# USB-C_Power_Delivery_Board.net
KiCad netlist of a schematic drawn in Altium Designer
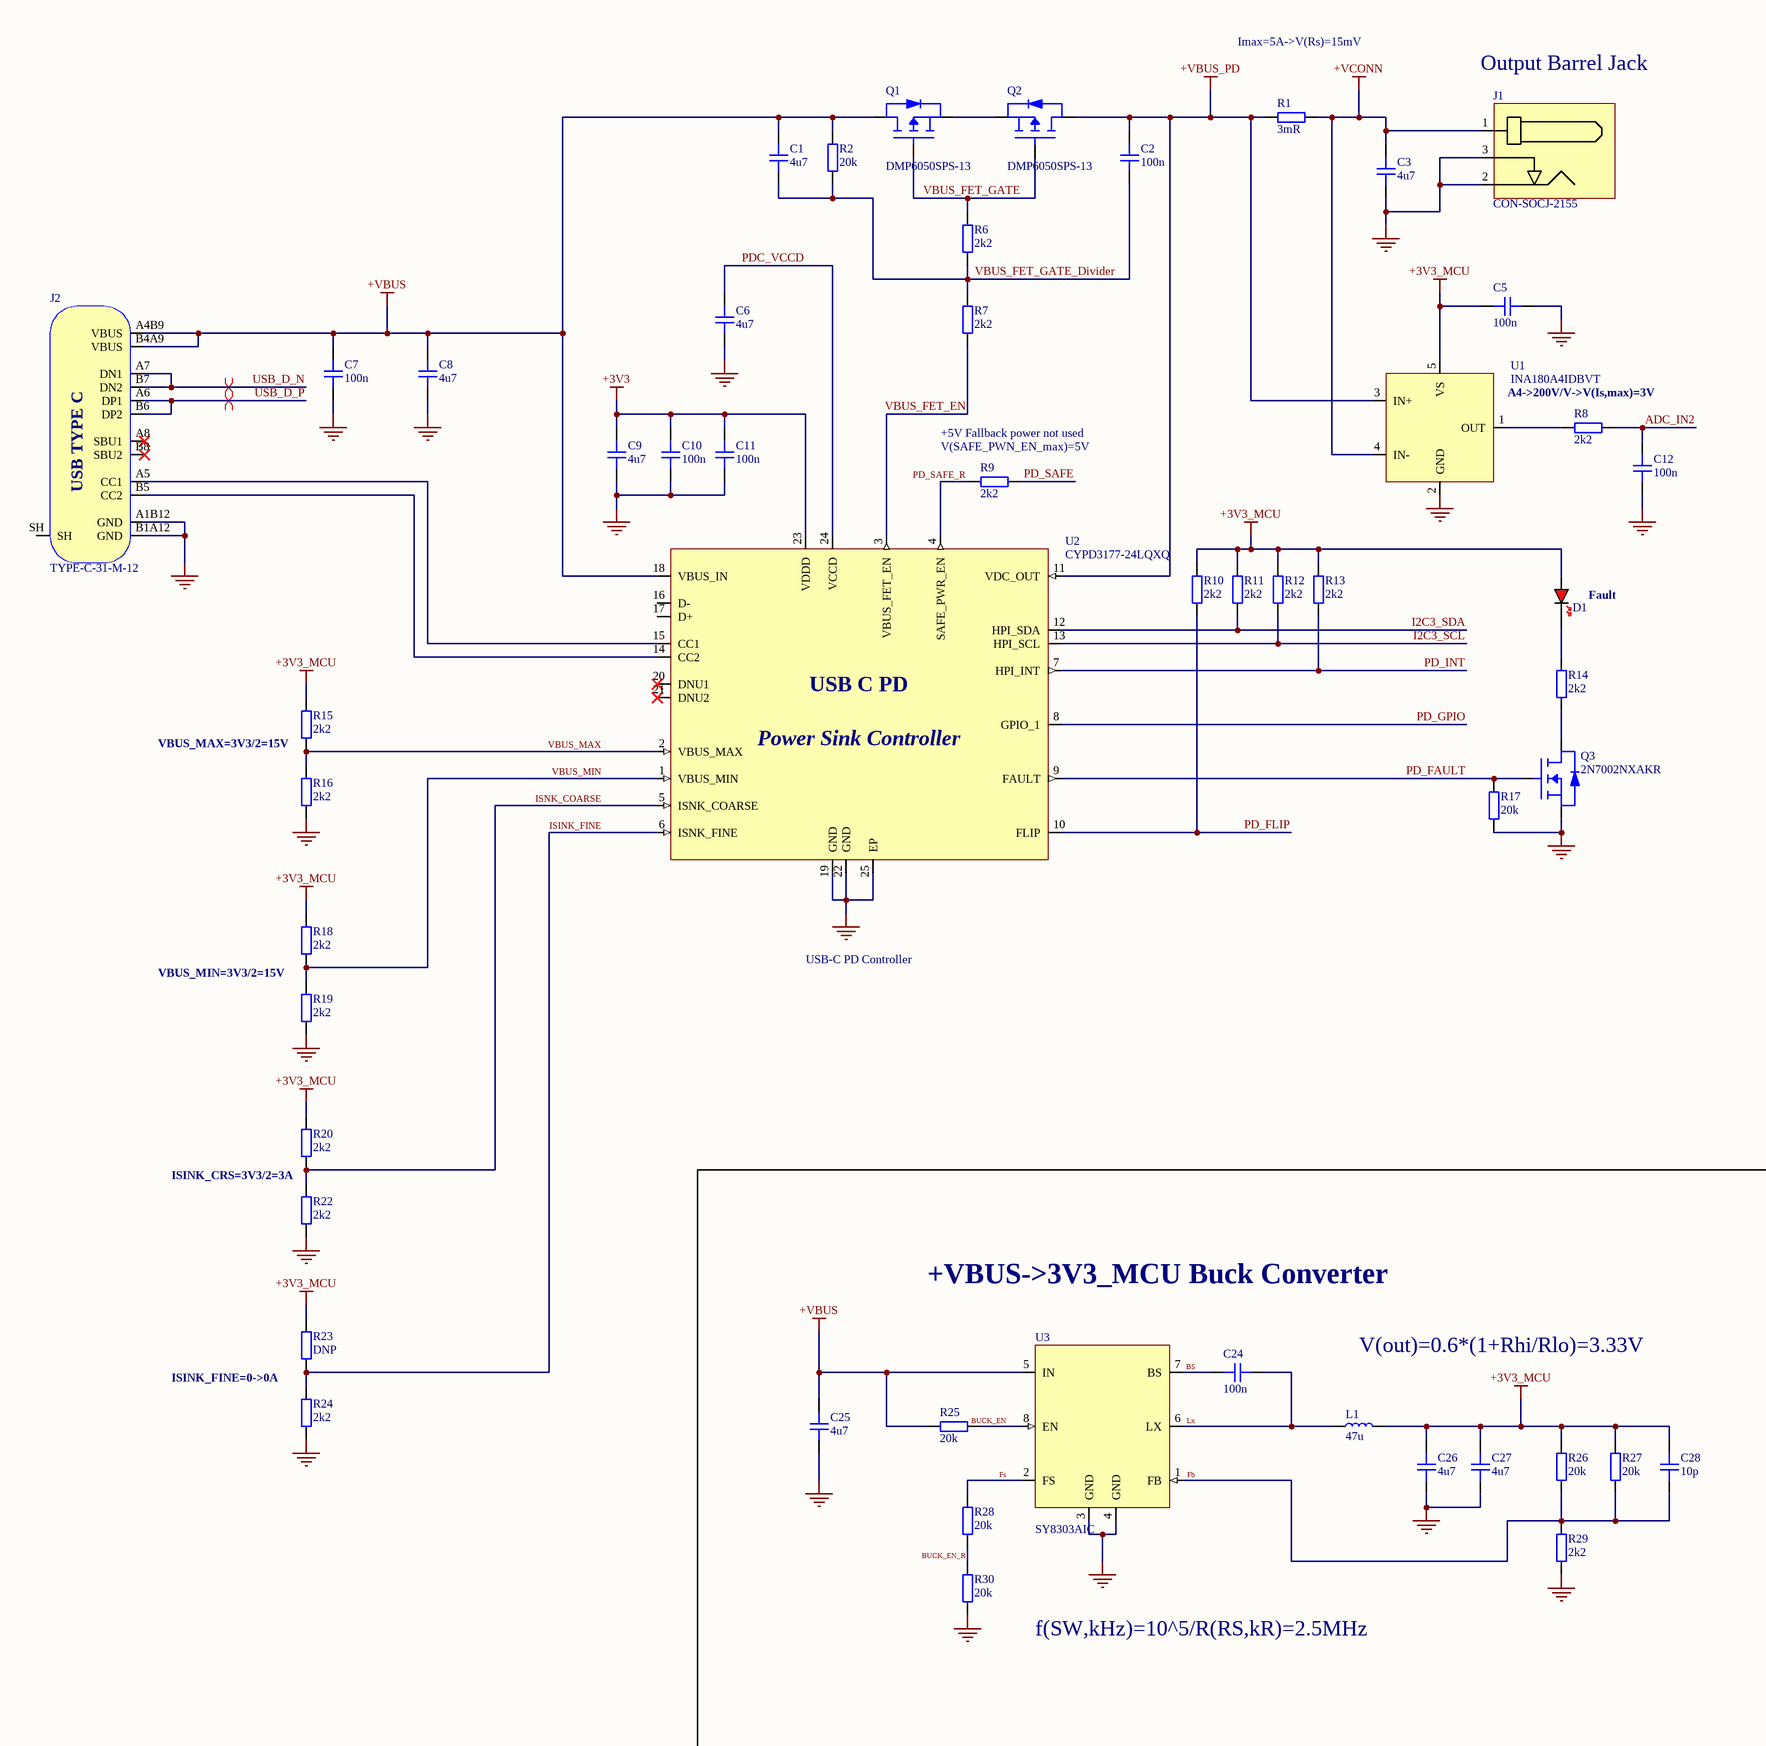
[diagram p0: USB-C Power Delivery Board.SchDoc, left]
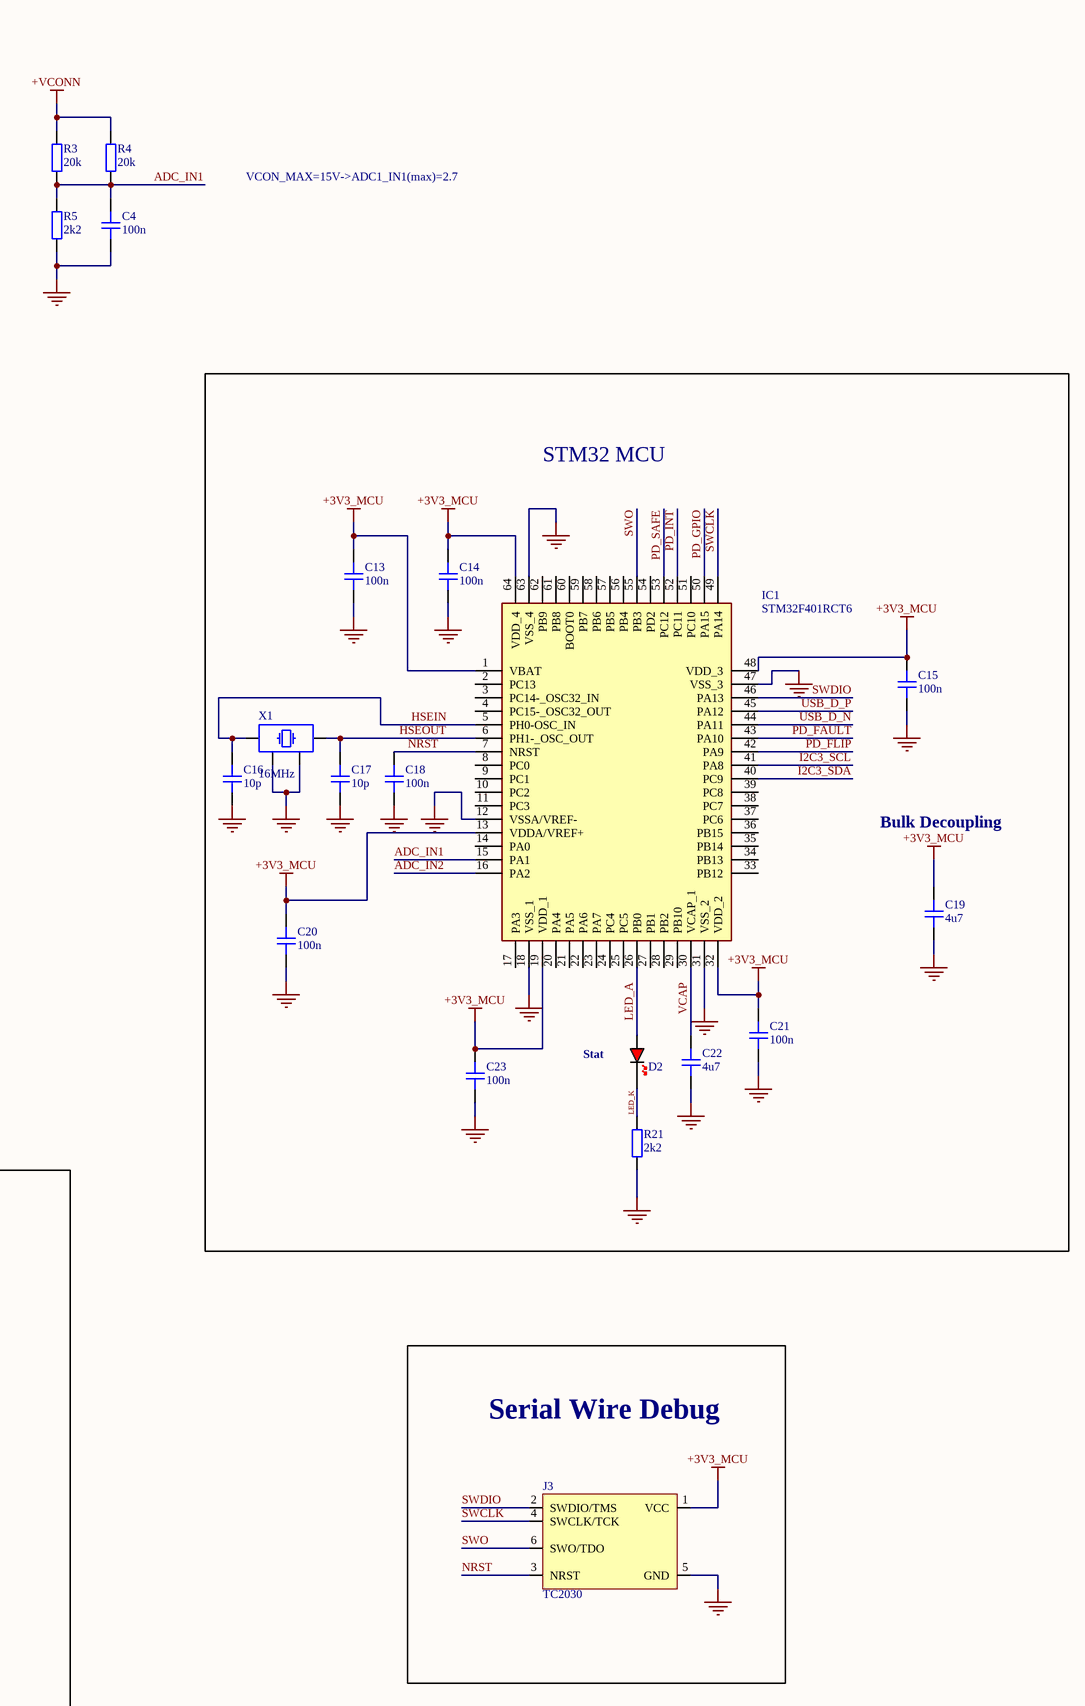
[diagram p1: USB-C Power Delivery Board.SchDoc, right]

(export (version "E")
  (design (tool "Eeschema 10.0.6"))
  (components
    (comp (ref "C1")
      (value "4u7")
      (footprint "CAP_0603")
      (description "Capacitor SMD 0603 50V")
      (libsource (lib "Schematic-Lib-PhilsLab") (part "CAP_0603_50V"))
    )
    (comp (ref "C2")
      (value "100n")
      (footprint "CAP_0402")
      (description "Capacitor SMD 0402 50V")
      (libsource (lib "Schematic-Lib-PhilsLab") (part "CAP_0402_50V"))
    )
    (comp (ref "C3")
      (value "4u7")
      (footprint "CAP_0603")
      (description "Capacitor SMD 0603 50V")
      (libsource (lib "Schematic-Lib-PhilsLab") (part "CAP_0603_50V"))
    )
    (comp (ref "C4")
      (value "100n")
      (footprint "CAP_0402")
      (description "Capacitor SMD 0402 50V")
      (libsource (lib "Schematic-Lib-PhilsLab") (part "CAP_0402_50V"))
    )
    (comp (ref "C5")
      (value "100n")
      (footprint "CAP_0402")
      (description "Capacitor SMD 0402 50V")
      (libsource (lib "Schematic-Lib-PhilsLab") (part "CAP_0402_50V"))
    )
    (comp (ref "C6")
      (value "4u7")
      (footprint "CAP_0603")
      (description "Capacitor SMD 0603 50V")
      (libsource (lib "Schematic-Lib-PhilsLab") (part "CAP_0603_50V"))
    )
    (comp (ref "C7")
      (value "100n")
      (footprint "CAP_0402")
      (description "Capacitor SMD 0402 50V")
      (libsource (lib "Schematic-Lib-PhilsLab") (part "CAP_0402_50V"))
    )
    (comp (ref "C8")
      (value "4u7")
      (footprint "CAP_0603")
      (description "Capacitor SMD 0603 50V")
      (libsource (lib "Schematic-Lib-PhilsLab") (part "CAP_0603_50V"))
    )
    (comp (ref "C9")
      (value "4u7")
      (footprint "CAP_0603")
      (description "Capacitor SMD 0603 50V")
      (libsource (lib "Schematic-Lib-PhilsLab") (part "CAP_0603_50V"))
    )
    (comp (ref "C10")
      (value "100n")
      (footprint "CAP_0402")
      (description "Capacitor SMD 0402 50V")
      (libsource (lib "Schematic-Lib-PhilsLab") (part "CAP_0402_50V"))
    )
    (comp (ref "C11")
      (value "100n")
      (footprint "CAP_0402")
      (description "Capacitor SMD 0402 50V")
      (libsource (lib "Schematic-Lib-PhilsLab") (part "CAP_0402_50V"))
    )
    (comp (ref "C12")
      (value "100n")
      (footprint "CAP_0402")
      (description "Capacitor SMD 0402 50V")
      (libsource (lib "Schematic-Lib-PhilsLab") (part "CAP_0402_50V"))
    )
    (comp (ref "C13")
      (value "100n")
      (footprint "CAP_0402")
      (description "Capacitor SMD 0402 50V")
      (libsource (lib "Schematic-Lib-PhilsLab") (part "CAP_0402_50V"))
    )
    (comp (ref "C14")
      (value "100n")
      (footprint "CAP_0402")
      (description "Capacitor SMD 0402 50V")
      (libsource (lib "Schematic-Lib-PhilsLab") (part "CAP_0402_50V"))
    )
    (comp (ref "C15")
      (value "100n")
      (footprint "CAP_0402")
      (description "Capacitor SMD 0402 50V")
      (libsource (lib "Schematic-Lib-PhilsLab") (part "CAP_0402_50V"))
    )
    (comp (ref "C16")
      (value "10p")
      (footprint "CAP_0402")
      (description "Capacitor SMD 0402 50V")
      (libsource (lib "Schematic-Lib-PhilsLab") (part "CAP_0402_50V"))
    )
    (comp (ref "C17")
      (value "10p")
      (footprint "CAP_0402")
      (description "Capacitor SMD 0402 50V")
      (libsource (lib "Schematic-Lib-PhilsLab") (part "CAP_0402_50V"))
    )
    (comp (ref "C18")
      (value "100n")
      (footprint "CAP_0402")
      (description "Capacitor SMD 0402 50V")
      (libsource (lib "Schematic-Lib-PhilsLab") (part "CAP_0402_50V"))
    )
    (comp (ref "C19")
      (value "4u7")
      (footprint "CAP_0603")
      (description "Capacitor SMD 0603 50V")
      (libsource (lib "Schematic-Lib-PhilsLab") (part "CAP_0603_50V"))
    )
    (comp (ref "C20")
      (value "100n")
      (footprint "CAP_0402")
      (description "Capacitor SMD 0402 50V")
      (libsource (lib "Schematic-Lib-PhilsLab") (part "CAP_0402_50V"))
    )
    (comp (ref "C21")
      (value "100n")
      (footprint "CAP_0402")
      (description "Capacitor SMD 0402 50V")
      (libsource (lib "Schematic-Lib-PhilsLab") (part "CAP_0402_50V"))
    )
    (comp (ref "C22")
      (value "4u7")
      (footprint "CAP_0603")
      (description "Capacitor SMD 0603 50V")
      (libsource (lib "Schematic-Lib-PhilsLab") (part "CAP_0603_50V"))
    )
    (comp (ref "C23")
      (value "100n")
      (footprint "CAP_0402")
      (description "Capacitor SMD 0402 50V")
      (libsource (lib "Schematic-Lib-PhilsLab") (part "CAP_0402_50V"))
    )
    (comp (ref "C24")
      (value "100n")
      (footprint "CAP_0402")
      (description "Capacitor SMD 0402 50V")
      (libsource (lib "Schematic-Lib-PhilsLab") (part "CAP_0402_50V"))
    )
    (comp (ref "C25")
      (value "4u7")
      (footprint "CAP_0603")
      (description "Capacitor SMD 0603 50V")
      (libsource (lib "Schematic-Lib-PhilsLab") (part "CAP_0603_50V"))
    )
    (comp (ref "C26")
      (value "4u7")
      (footprint "CAP_0603")
      (description "Capacitor SMD 0603 50V")
      (libsource (lib "Schematic-Lib-PhilsLab") (part "CAP_0603_50V"))
    )
    (comp (ref "C27")
      (value "4u7")
      (footprint "CAP_0603")
      (description "Capacitor SMD 0603 50V")
      (libsource (lib "Schematic-Lib-PhilsLab") (part "CAP_0603_50V"))
    )
    (comp (ref "C28")
      (value "10p")
      (footprint "CAP_0402")
      (description "Capacitor SMD 0402 50V")
      (libsource (lib "Schematic-Lib-PhilsLab") (part "CAP_0402_50V"))
    )
    (comp (ref "D1")
      (value "RED")
      (footprint "LED_0402_RED")
      (description "LED 0402 RED SMD")
      (libsource (lib "Schematic-Lib-PhilsLab") (part "LED_0402_RED"))
    )
    (comp (ref "D2")
      (value "RED")
      (footprint "LED_0402_RED")
      (description "LED 0402 RED SMD")
      (libsource (lib "Schematic-Lib-PhilsLab") (part "LED_0402_RED"))
    )
    (comp (ref "IC1")
      (value "STM32F401RCT6")
      (footprint "SamacSys:QFP50P1200X1200X160-64N")
      (description "Integrated Circuit")
      (fields (field (name "MOUSER PART NUMBER") "511-STM32F401RCT6"))
      (libsource (lib "*") (part "STM32F401RCT6"))
    )
    (comp (ref "J1")
      (value "CON-SOCJ-2155")
      (footprint "CON-SOCJ-2155")
      (description "DC Barrell Jack 2.1mm 30V 2.5A THT")
      (fields (field (name "MANUFACTURER") "Gravitech"))
      (libsource (lib "Schematic-Lib-PhilsLab") (part "CON-SOCJ-2155"))
    )
    (comp (ref "J2")
      (value "TYPE-C-31-M-12")
      (footprint "TYPE-C-31-M-12")
      (description "USB Type C Connector Horizontal SMT")
      (fields (field (name "MANUFACTURER") "Koren Hroparts"))
      (libsource (lib "Schematic-Lib-PhilsLab") (part "TYPE-C-31-M-12"))
    )
    (comp (ref "J3")
      (value "TC2030")
      (footprint "TC2030-FP")
      (description "Tag-Connect No-Solder SWD Debug Connector DO NOT PLACE")
      (fields (field (name "MANUFACTURER") "Tag-Connect"))
      (libsource (lib "Schematic-Lib-PhilsLab") (part "TC2030"))
    )
    (comp (ref "L1")
      (value "47u")
      (footprint "SPM10065VT-220M-D")
      (description "Inductor SMD 47uH 4A 20%")
      (fields
        (field (name "MANUFACTURER") "TDK")
        (field (name "MANUFACTURER PART NUMBER") "SPM10065VT-470M-D")
      )
      (libsource (lib "Schematic-Lib-PhilsLab") (part "SPM10065VT-470M-D"))
    )
    (comp (ref "Q1")
      (value "DMP6050SPS-13")
      (footprint "PowerDI5060-8")
      (description "MOSFET P-Channel Vds=60V Vgs=+-20V Id=26A Rds(on¦=50mOhms")
      (fields (field (name "MANUFACTURER") "Diodes Incorporated"))
      (libsource (lib "Schematic-Lib-PhilsLab") (part "DMP6050SPS-13"))
    )
    (comp (ref "Q2")
      (value "DMP6050SPS-13")
      (footprint "PowerDI5060-8")
      (description "MOSFET P-Channel Vds=60V Vgs=+-20V Id=26A Rds(on¦=50mOhms")
      (fields (field (name "MANUFACTURER") "Diodes Incorporated"))
      (libsource (lib "Schematic-Lib-PhilsLab") (part "DMP6050SPS-13"))
    )
    (comp (ref "Q3")
      (value "2N7002NXAKR")
      (footprint "SSM3J338R,LF-SOT23-F")
      (description "MOSFET N-Channel Vds=60V Id=300mA with ESD Protection")
      (fields (field (name "MANUFACTURER") "Nexperia"))
      (libsource (lib "Schematic-Lib-PhilsLab") (part "2N7002NXAKR"))
    )
    (comp (ref "R1")
      (value "3mR")
      (footprint "RES_5931")
      (description "Current Sense Resistor SMD 0805")
      (libsource (lib "Schematic-Lib-PhilsLab") (part "RES_5931"))
    )
    (comp (ref "R2")
      (value "20k")
      (footprint "RES_0402")
      (description "Resistor SMD 0402")
      (libsource (lib "Schematic-Lib-PhilsLab") (part "RES_0402"))
    )
    (comp (ref "R3")
      (value "20k")
      (footprint "RES_0402")
      (description "Resistor SMD 0402")
      (libsource (lib "Schematic-Lib-PhilsLab") (part "RES_0402"))
    )
    (comp (ref "R4")
      (value "20k")
      (footprint "RES_0402")
      (description "Resistor SMD 0402")
      (libsource (lib "Schematic-Lib-PhilsLab") (part "RES_0402"))
    )
    (comp (ref "R5")
      (value "2k2")
      (footprint "RES_0402")
      (description "Resistor SMD 0402")
      (libsource (lib "Schematic-Lib-PhilsLab") (part "RES_0402"))
    )
    (comp (ref "R6")
      (value "2k2")
      (footprint "RES_0402")
      (description "Resistor SMD 0402")
      (libsource (lib "Schematic-Lib-PhilsLab") (part "RES_0402"))
    )
    (comp (ref "R7")
      (value "2k2")
      (footprint "RES_0402")
      (description "Resistor SMD 0402")
      (libsource (lib "Schematic-Lib-PhilsLab") (part "RES_0402"))
    )
    (comp (ref "R8")
      (value "2k2")
      (footprint "RES_0402")
      (description "Resistor SMD 0402")
      (libsource (lib "Schematic-Lib-PhilsLab") (part "RES_0402"))
    )
    (comp (ref "R9")
      (value "2k2")
      (footprint "RES_0402")
      (description "Resistor SMD 0402")
      (libsource (lib "Schematic-Lib-PhilsLab") (part "RES_0402"))
    )
    (comp (ref "R10")
      (value "2k2")
      (footprint "RES_0402")
      (description "Resistor SMD 0402")
      (libsource (lib "Schematic-Lib-PhilsLab") (part "RES_0402"))
    )
    (comp (ref "R11")
      (value "2k2")
      (footprint "RES_0402")
      (description "Resistor SMD 0402")
      (libsource (lib "Schematic-Lib-PhilsLab") (part "RES_0402"))
    )
    (comp (ref "R12")
      (value "2k2")
      (footprint "RES_0402")
      (description "Resistor SMD 0402")
      (libsource (lib "Schematic-Lib-PhilsLab") (part "RES_0402"))
    )
    (comp (ref "R13")
      (value "2k2")
      (footprint "RES_0402")
      (description "Resistor SMD 0402")
      (libsource (lib "Schematic-Lib-PhilsLab") (part "RES_0402"))
    )
    (comp (ref "R14")
      (value "2k2")
      (footprint "RES_0402")
      (description "Resistor SMD 0402")
      (libsource (lib "Schematic-Lib-PhilsLab") (part "RES_0402"))
    )
    (comp (ref "R15")
      (value "2k2")
      (footprint "RES_0402")
      (description "Resistor SMD 0402")
      (libsource (lib "Schematic-Lib-PhilsLab") (part "RES_0402"))
    )
    (comp (ref "R16")
      (value "2k2")
      (footprint "RES_0402")
      (description "Resistor SMD 0402")
      (libsource (lib "Schematic-Lib-PhilsLab") (part "RES_0402"))
    )
    (comp (ref "R17")
      (value "20k")
      (footprint "RES_0402")
      (description "Resistor SMD 0402")
      (libsource (lib "Schematic-Lib-PhilsLab") (part "RES_0402"))
    )
    (comp (ref "R18")
      (value "2k2")
      (footprint "RES_0402")
      (description "Resistor SMD 0402")
      (libsource (lib "Schematic-Lib-PhilsLab") (part "RES_0402"))
    )
    (comp (ref "R19")
      (value "2k2")
      (footprint "RES_0402")
      (description "Resistor SMD 0402")
      (libsource (lib "Schematic-Lib-PhilsLab") (part "RES_0402"))
    )
    (comp (ref "R20")
      (value "2k2")
      (footprint "RES_0402")
      (description "Resistor SMD 0402")
      (libsource (lib "Schematic-Lib-PhilsLab") (part "RES_0402"))
    )
    (comp (ref "R21")
      (value "2k2")
      (footprint "RES_0402")
      (description "Resistor SMD 0402")
      (libsource (lib "Schematic-Lib-PhilsLab") (part "RES_0402"))
    )
    (comp (ref "R22")
      (value "2k2")
      (footprint "RES_0402")
      (description "Resistor SMD 0402")
      (libsource (lib "Schematic-Lib-PhilsLab") (part "RES_0402"))
    )
    (comp (ref "R23")
      (value "DNP")
      (footprint "RES_0402")
      (description "Resistor SMD 0402")
      (libsource (lib "Schematic-Lib-PhilsLab") (part "RES_0402"))
    )
    (comp (ref "R24")
      (value "2k2")
      (footprint "RES_0402")
      (description "Resistor SMD 0402")
      (libsource (lib "Schematic-Lib-PhilsLab") (part "RES_0402"))
    )
    (comp (ref "R25")
      (value "20k")
      (footprint "RES_0402")
      (description "Resistor SMD 0402")
      (libsource (lib "Schematic-Lib-PhilsLab") (part "RES_0402"))
    )
    (comp (ref "R26")
      (value "20k")
      (footprint "RES_0402")
      (description "Resistor SMD 0402")
      (libsource (lib "Schematic-Lib-PhilsLab") (part "RES_0402"))
    )
    (comp (ref "R27")
      (value "20k")
      (footprint "RES_0402")
      (description "Resistor SMD 0402")
      (libsource (lib "Schematic-Lib-PhilsLab") (part "RES_0402"))
    )
    (comp (ref "R28")
      (value "20k")
      (footprint "RES_0402")
      (description "Resistor SMD 0402")
      (libsource (lib "Schematic-Lib-PhilsLab") (part "RES_0402"))
    )
    (comp (ref "R29")
      (value "2k2")
      (footprint "RES_0402")
      (description "Resistor SMD 0402")
      (libsource (lib "Schematic-Lib-PhilsLab") (part "RES_0402"))
    )
    (comp (ref "R30")
      (value "20k")
      (footprint "RES_0402")
      (description "Resistor SMD 0402")
      (libsource (lib "Schematic-Lib-PhilsLab") (part "RES_0402"))
    )
    (comp (ref "U1")
      (value "INA180A4IDBVT")
      (footprint "SOT-23-5")
      (description "Current Sense Amplifier 200V/V Gain 105kHz BW SOT-23-5")
      (fields (field (name "MANUFACTURER") "Texas Instruments"))
      (libsource (lib "Schematic-Lib-PhilsLab") (part "INA180A4IDBVT"))
    )
    (comp (ref "U2")
      (value "CYPD3177-24LQXQ")
      (footprint "QFN-24-0MM5")
      (description "USB Type-C Port Controller for Power Sinks")
      (fields (field (name "MANUFACTURER") "Cypress Semicon"))
      (libsource (lib "Schematic-Lib-PhilsLab") (part "CYPD3177-24LQXQ"))
    )
    (comp (ref "U3")
      (value "SY8303AIC")
      (footprint "TSOT23-8")
      (description "High Efficiency Fast Response, 3A, 40V Input Synchronous Step Down Regulator")
      (fields (field (name "MANUFACTURER") "Silergy"))
      (libsource (lib "Schematic-Lib-PhilsLab") (part "SY8303AIC"))
    )
    (comp (ref "X1")
      (value "16MHz")
      (footprint "XTAL_2520")
      (description "Crystal SMD 2520")
      (libsource (lib "Schematic-Lib-PhilsLab") (part "XTAL_2520"))
    )
  )
  (nets
    (net (code "1") (name "+3V3") (class "Default")
      (node (ref "C10") (pin "2") (pinfunction "2_2") (pintype "passive"))
      (node (ref "C11") (pin "2") (pinfunction "2_2") (pintype "passive"))
      (node (ref "C9") (pin "2") (pinfunction "2_2") (pintype "passive"))
      (node (ref "U2") (pin "23") (pinfunction "VDDD_23") (pintype "power_in"))
    )
    (net (code "2") (name "+3V3_MCU") (class "Default")
      (node (ref "C13") (pin "1") (pinfunction "1_1") (pintype "passive"))
      (node (ref "C14") (pin "1") (pinfunction "1_1") (pintype "passive"))
      (node (ref "C15") (pin "1") (pinfunction "1_1") (pintype "passive"))
      (node (ref "C19") (pin "2") (pinfunction "2_2") (pintype "passive"))
      (node (ref "C20") (pin "1") (pinfunction "1_1") (pintype "passive"))
      (node (ref "C21") (pin "1") (pinfunction "1_1") (pintype "passive"))
      (node (ref "C23") (pin "1") (pinfunction "1_1") (pintype "passive"))
      (node (ref "C26") (pin "1") (pinfunction "1_1") (pintype "passive"))
      (node (ref "C27") (pin "1") (pinfunction "1_1") (pintype "passive"))
      (node (ref "C28") (pin "1") (pinfunction "1_1") (pintype "passive"))
      (node (ref "C5") (pin "2") (pinfunction "2_2") (pintype "passive"))
      (node (ref "D1") (pin "A") (pinfunction "A_A") (pintype "passive"))
      (node (ref "IC1") (pin "1") (pinfunction "VBAT_1") (pintype "passive"))
      (node (ref "IC1") (pin "13") (pinfunction "VDDA/VREF+_13") (pintype "passive"))
      (node (ref "IC1") (pin "19") (pinfunction "VDD_1_19") (pintype "passive"))
      (node (ref "IC1") (pin "32") (pinfunction "VDD_2_32") (pintype "passive"))
      (node (ref "IC1") (pin "48") (pinfunction "VDD_3_48") (pintype "passive"))
      (node (ref "IC1") (pin "64") (pinfunction "VDD_4_64") (pintype "passive"))
      (node (ref "J3") (pin "1") (pinfunction "VCC_1") (pintype "passive"))
      (node (ref "L1") (pin "2") (pinfunction "2_2") (pintype "passive"))
      (node (ref "R10") (pin "1") (pinfunction "1_1") (pintype "passive"))
      (node (ref "R11") (pin "1") (pinfunction "1_1") (pintype "passive"))
      (node (ref "R12") (pin "1") (pinfunction "1_1") (pintype "passive"))
      (node (ref "R13") (pin "1") (pinfunction "1_1") (pintype "passive"))
      (node (ref "R15") (pin "2") (pinfunction "2_2") (pintype "passive"))
      (node (ref "R18") (pin "2") (pinfunction "2_2") (pintype "passive"))
      (node (ref "R20") (pin "2") (pinfunction "2_2") (pintype "passive"))
      (node (ref "R23") (pin "2") (pinfunction "2_2") (pintype "passive"))
      (node (ref "R26") (pin "2") (pinfunction "2_2") (pintype "passive"))
      (node (ref "R27") (pin "2") (pinfunction "2_2") (pintype "passive"))
      (node (ref "U1") (pin "5") (pinfunction "VS_5") (pintype "passive"))
    )
    (net (code "3") (name "+VBUS") (class "Default")
      (node (ref "C1") (pin "2") (pinfunction "2_2") (pintype "passive"))
      (node (ref "C25") (pin "2") (pinfunction "2_2") (pintype "passive"))
      (node (ref "C7") (pin "2") (pinfunction "2_2") (pintype "passive"))
      (node (ref "C8") (pin "2") (pinfunction "2_2") (pintype "passive"))
      (node (ref "J2") (pin "A4B9") (pinfunction "VBUS_A4B9") (pintype "power_in"))
      (node (ref "J2") (pin "B4A9") (pinfunction "VBUS_B4A9") (pintype "power_in"))
      (node (ref "Q1") (pin "1") (pinfunction "D_1") (pintype "passive"))
      (node (ref "R2") (pin "2") (pinfunction "2_2") (pintype "passive"))
      (node (ref "R25") (pin "1") (pinfunction "1_1") (pintype "passive"))
      (node (ref "U2") (pin "18") (pinfunction "VBUS_IN_18") (pintype "power_in"))
      (node (ref "U3") (pin "5") (pinfunction "IN_5") (pintype "power_in"))
    )
    (net (code "4") (name "+VBUS_PD") (class "Default")
      (node (ref "C2") (pin "2") (pinfunction "2_2") (pintype "passive"))
      (node (ref "Q2") (pin "1") (pinfunction "D_1") (pintype "passive"))
      (node (ref "R1") (pin "2") (pinfunction "2_2") (pintype "passive"))
      (node (ref "U1") (pin "3") (pinfunction "IN+_3") (pintype "passive"))
      (node (ref "U2") (pin "11") (pinfunction "VDC_OUT_11") (pintype "input"))
    )
    (net (code "5") (name "+VCONN") (class "Default")
      (node (ref "C3") (pin "2") (pinfunction "2_2") (pintype "passive"))
      (node (ref "J1") (pin "1") (pinfunction "1_1") (pintype "passive"))
      (node (ref "R1") (pin "1") (pinfunction "1_1") (pintype "passive"))
      (node (ref "R3") (pin "1") (pinfunction "1_1") (pintype "passive"))
      (node (ref "R4") (pin "1") (pinfunction "1_1") (pintype "passive"))
      (node (ref "U1") (pin "4") (pinfunction "IN-_4") (pintype "passive"))
    )
    (net (code "6") (name "/ADC_IN1") (class "Default")
      (node (ref "C4") (pin "1") (pinfunction "1_1") (pintype "passive"))
      (node (ref "IC1") (pin "15") (pinfunction "PA1_15") (pintype "passive"))
      (node (ref "R3") (pin "2") (pinfunction "2_2") (pintype "passive"))
      (node (ref "R4") (pin "2") (pinfunction "2_2") (pintype "passive"))
      (node (ref "R5") (pin "1") (pinfunction "1_1") (pintype "passive"))
    )
    (net (code "7") (name "/ADC_IN2") (class "Default")
      (node (ref "C12") (pin "1") (pinfunction "1_1") (pintype "passive"))
      (node (ref "IC1") (pin "16") (pinfunction "PA2_16") (pintype "passive"))
      (node (ref "R8") (pin "1") (pinfunction "1_1") (pintype "passive"))
    )
    (net (code "8") (name "/BS") (class "Default")
      (node (ref "C24") (pin "1") (pinfunction "1_1") (pintype "passive"))
      (node (ref "U3") (pin "7") (pinfunction "BS_7") (pintype "power_in"))
    )
    (net (code "9") (name "/BUCK_EN") (class "Default")
      (node (ref "R25") (pin "2") (pinfunction "2_2") (pintype "passive"))
      (node (ref "U3") (pin "8") (pinfunction "EN_8") (pintype "input"))
    )
    (net (code "10") (name "/BUCK_EN_R") (class "Default")
      (node (ref "R28") (pin "2") (pinfunction "2_2") (pintype "passive"))
      (node (ref "R30") (pin "1") (pinfunction "1_1") (pintype "passive"))
    )
    (net (code "11") (name "/Fb") (class "Default")
      (node (ref "C28") (pin "2") (pinfunction "2_2") (pintype "passive"))
      (node (ref "R26") (pin "1") (pinfunction "1_1") (pintype "passive"))
      (node (ref "R27") (pin "1") (pinfunction "1_1") (pintype "passive"))
      (node (ref "R29") (pin "1") (pinfunction "1_1") (pintype "passive"))
      (node (ref "U3") (pin "1") (pinfunction "FB_1") (pintype "input"))
    )
    (net (code "12") (name "/Fs") (class "Default")
      (node (ref "R28") (pin "1") (pinfunction "1_1") (pintype "passive"))
      (node (ref "U3") (pin "2") (pinfunction "FS_2") (pintype "passive"))
    )
    (net (code "13") (name "/HSEIN") (class "Default")
      (node (ref "C16") (pin "1") (pinfunction "1_1") (pintype "passive"))
      (node (ref "IC1") (pin "5") (pinfunction "PH0-OSC_IN_5") (pintype "passive"))
      (node (ref "X1") (pin "1") (pinfunction "1_1") (pintype "passive"))
    )
    (net (code "14") (name "/HSEOUT") (class "Default")
      (node (ref "C17") (pin "1") (pinfunction "1_1") (pintype "passive"))
      (node (ref "IC1") (pin "6") (pinfunction "PH1-_OSC_OUT_6") (pintype "passive"))
      (node (ref "X1") (pin "3") (pinfunction "3_3") (pintype "passive"))
    )
    (net (code "15") (name "/I2C3_SCL") (class "Default")
      (node (ref "IC1") (pin "41") (pinfunction "PA8_41") (pintype "passive"))
      (node (ref "R12") (pin "2") (pinfunction "2_2") (pintype "passive"))
      (node (ref "U2") (pin "13") (pinfunction "HPI_SCL_13") (pintype "open_collector"))
    )
    (net (code "16") (name "/I2C3_SDA") (class "Default")
      (node (ref "IC1") (pin "40") (pinfunction "PC9_40") (pintype "passive"))
      (node (ref "R11") (pin "2") (pinfunction "2_2") (pintype "passive"))
      (node (ref "U2") (pin "12") (pinfunction "HPI_SDA_12") (pintype "open_collector"))
    )
    (net (code "17") (name "/ISINK_FINE") (class "Default")
      (node (ref "R23") (pin "1") (pinfunction "1_1") (pintype "passive"))
      (node (ref "R24") (pin "2") (pinfunction "2_2") (pintype "passive"))
      (node (ref "U2") (pin "6") (pinfunction "ISNK_FINE_6") (pintype "input"))
    )
    (net (code "18") (name "/ISNK_COARSE") (class "Default")
      (node (ref "R20") (pin "1") (pinfunction "1_1") (pintype "passive"))
      (node (ref "R22") (pin "2") (pinfunction "2_2") (pintype "passive"))
      (node (ref "U2") (pin "5") (pinfunction "ISNK_COARSE_5") (pintype "input"))
    )
    (net (code "19") (name "/LED_A") (class "Default")
      (node (ref "D2") (pin "A") (pinfunction "A_A") (pintype "passive"))
      (node (ref "IC1") (pin "26") (pinfunction "PB0_26") (pintype "passive"))
    )
    (net (code "20") (name "/LED_K") (class "Default")
      (node (ref "D2") (pin "K") (pinfunction "K_K") (pintype "passive"))
      (node (ref "R21") (pin "1") (pinfunction "1_1") (pintype "passive"))
    )
    (net (code "21") (name "/Lx") (class "Default")
      (node (ref "C24") (pin "2") (pinfunction "2_2") (pintype "passive"))
      (node (ref "L1") (pin "1") (pinfunction "1_1") (pintype "passive"))
      (node (ref "U3") (pin "6") (pinfunction "LX_6") (pintype "power_in"))
    )
    (net (code "22") (name "/NRST") (class "Default")
      (node (ref "C18") (pin "1") (pinfunction "1_1") (pintype "passive"))
      (node (ref "IC1") (pin "7") (pinfunction "NRST_7") (pintype "passive"))
      (node (ref "J3") (pin "3") (pinfunction "NRST_3") (pintype "passive"))
    )
    (net (code "23") (name "/PDC_VCCD") (class "Default")
      (node (ref "C6") (pin "2") (pinfunction "2_2") (pintype "passive"))
      (node (ref "U2") (pin "24") (pinfunction "VCCD_24") (pintype "power_in"))
    )
    (net (code "24") (name "/PD_FAULT") (class "Default")
      (node (ref "IC1") (pin "43") (pinfunction "PA10_43") (pintype "passive"))
      (node (ref "Q3") (pin "G") (pinfunction "G_G") (pintype "passive"))
      (node (ref "R17") (pin "2") (pinfunction "2_2") (pintype "passive"))
      (node (ref "U2") (pin "9") (pinfunction "FAULT_9") (pintype "output"))
    )
    (net (code "25") (name "/PD_FLIP") (class "Default")
      (node (ref "IC1") (pin "42") (pinfunction "PA9_42") (pintype "passive"))
      (node (ref "R10") (pin "2") (pinfunction "2_2") (pintype "passive"))
      (node (ref "U2") (pin "10") (pinfunction "FLIP_10") (pintype "open_collector"))
    )
    (net (code "26") (name "/PD_GPIO") (class "Default")
      (node (ref "IC1") (pin "50") (pinfunction "PA15_50") (pintype "passive"))
      (node (ref "U2") (pin "8") (pinfunction "GPIO_1_8") (pintype "bidirectional"))
    )
    (net (code "27") (name "/PD_INT") (class "Default")
      (node (ref "IC1") (pin "52") (pinfunction "PC11_52") (pintype "passive"))
      (node (ref "R13") (pin "2") (pinfunction "2_2") (pintype "passive"))
      (node (ref "U2") (pin "7") (pinfunction "HPI_INT_7") (pintype "output"))
    )
    (net (code "28") (name "/PD_SAFE") (class "Default")
      (node (ref "IC1") (pin "53") (pinfunction "PC12_53") (pintype "passive"))
      (node (ref "R9") (pin "1") (pinfunction "1_1") (pintype "passive"))
    )
    (net (code "29") (name "/PD_SAFE_R") (class "Default")
      (node (ref "R9") (pin "2") (pinfunction "2_2") (pintype "passive"))
      (node (ref "U2") (pin "4") (pinfunction "SAFE_PWR_EN_4") (pintype "output"))
    )
    (net (code "30") (name "/SWCLK") (class "Default")
      (node (ref "IC1") (pin "49") (pinfunction "PA14_49") (pintype "passive"))
      (node (ref "J3") (pin "4") (pinfunction "SWCLK/TCK_4") (pintype "passive"))
    )
    (net (code "31") (name "/SWDIO") (class "Default")
      (node (ref "IC1") (pin "46") (pinfunction "PA13_46") (pintype "passive"))
      (node (ref "J3") (pin "2") (pinfunction "SWDIO/TMS_2") (pintype "passive"))
    )
    (net (code "32") (name "/SWO") (class "Default")
      (node (ref "IC1") (pin "55") (pinfunction "PB3_55") (pintype "passive"))
      (node (ref "J3") (pin "6") (pinfunction "SWO/TDO_6") (pintype "passive"))
    )
    (net (code "33") (name "/USB_D_N") (class "Default")
      (node (ref "IC1") (pin "44") (pinfunction "PA11_44") (pintype "passive"))
      (node (ref "J2") (pin "A7") (pinfunction "DN1_A7") (pintype "bidirectional"))
      (node (ref "J2") (pin "B7") (pinfunction "DN2_B7") (pintype "bidirectional"))
    )
    (net (code "34") (name "/USB_D_P") (class "Default")
      (node (ref "IC1") (pin "45") (pinfunction "PA12_45") (pintype "passive"))
      (node (ref "J2") (pin "A6") (pinfunction "DP1_A6") (pintype "bidirectional"))
      (node (ref "J2") (pin "B6") (pinfunction "DP2_B6") (pintype "bidirectional"))
    )
    (net (code "35") (name "/VBUS_FET_EN") (class "Default")
      (node (ref "R7") (pin "1") (pinfunction "1_1") (pintype "passive"))
      (node (ref "U2") (pin "3") (pinfunction "VBUS_FET_EN_3") (pintype "output"))
    )
    (net (code "36") (name "/VBUS_FET_GATE") (class "Default")
      (node (ref "Q1") (pin "2") (pinfunction "G_2") (pintype "passive"))
      (node (ref "Q2") (pin "2") (pinfunction "G_2") (pintype "passive"))
      (node (ref "R6") (pin "2") (pinfunction "2_2") (pintype "passive"))
    )
    (net (code "37") (name "/VBUS_FET_GATE_Divider") (class "Default")
      (node (ref "C1") (pin "1") (pinfunction "1_1") (pintype "passive"))
      (node (ref "C2") (pin "1") (pinfunction "1_1") (pintype "passive"))
      (node (ref "R2") (pin "1") (pinfunction "1_1") (pintype "passive"))
      (node (ref "R6") (pin "1") (pinfunction "1_1") (pintype "passive"))
      (node (ref "R7") (pin "2") (pinfunction "2_2") (pintype "passive"))
    )
    (net (code "38") (name "/VBUS_MAX") (class "Default")
      (node (ref "R15") (pin "1") (pinfunction "1_1") (pintype "passive"))
      (node (ref "R16") (pin "2") (pinfunction "2_2") (pintype "passive"))
      (node (ref "U2") (pin "2") (pinfunction "VBUS_MAX_2") (pintype "input"))
    )
    (net (code "39") (name "/VBUS_MIN") (class "Default")
      (node (ref "R18") (pin "1") (pinfunction "1_1") (pintype "passive"))
      (node (ref "R19") (pin "2") (pinfunction "2_2") (pintype "passive"))
      (node (ref "U2") (pin "1") (pinfunction "VBUS_MIN_1") (pintype "input"))
    )
    (net (code "40") (name "/VCAP") (class "Default")
      (node (ref "C22") (pin "2") (pinfunction "2_2") (pintype "passive"))
      (node (ref "IC1") (pin "30") (pinfunction "VCAP_1_30") (pintype "passive"))
    )
    (net (code "41") (name "GND") (class "Default")
      (node (ref "C10") (pin "1") (pinfunction "1_1") (pintype "passive"))
      (node (ref "C11") (pin "1") (pinfunction "1_1") (pintype "passive"))
      (node (ref "C12") (pin "2") (pinfunction "2_2") (pintype "passive"))
      (node (ref "C13") (pin "2") (pinfunction "2_2") (pintype "passive"))
      (node (ref "C14") (pin "2") (pinfunction "2_2") (pintype "passive"))
      (node (ref "C15") (pin "2") (pinfunction "2_2") (pintype "passive"))
      (node (ref "C16") (pin "2") (pinfunction "2_2") (pintype "passive"))
      (node (ref "C17") (pin "2") (pinfunction "2_2") (pintype "passive"))
      (node (ref "C18") (pin "2") (pinfunction "2_2") (pintype "passive"))
      (node (ref "C19") (pin "1") (pinfunction "1_1") (pintype "passive"))
      (node (ref "C20") (pin "2") (pinfunction "2_2") (pintype "passive"))
      (node (ref "C21") (pin "2") (pinfunction "2_2") (pintype "passive"))
      (node (ref "C22") (pin "1") (pinfunction "1_1") (pintype "passive"))
      (node (ref "C23") (pin "2") (pinfunction "2_2") (pintype "passive"))
      (node (ref "C25") (pin "1") (pinfunction "1_1") (pintype "passive"))
      (node (ref "C26") (pin "2") (pinfunction "2_2") (pintype "passive"))
      (node (ref "C27") (pin "2") (pinfunction "2_2") (pintype "passive"))
      (node (ref "C3") (pin "1") (pinfunction "1_1") (pintype "passive"))
      (node (ref "C4") (pin "2") (pinfunction "2_2") (pintype "passive"))
      (node (ref "C5") (pin "1") (pinfunction "1_1") (pintype "passive"))
      (node (ref "C6") (pin "1") (pinfunction "1_1") (pintype "passive"))
      (node (ref "C7") (pin "1") (pinfunction "1_1") (pintype "passive"))
      (node (ref "C8") (pin "1") (pinfunction "1_1") (pintype "passive"))
      (node (ref "C9") (pin "1") (pinfunction "1_1") (pintype "passive"))
      (node (ref "IC1") (pin "12") (pinfunction "VSSA/VREF-_12") (pintype "passive"))
      (node (ref "IC1") (pin "18") (pinfunction "VSS_1_18") (pintype "passive"))
      (node (ref "IC1") (pin "31") (pinfunction "VSS_2_31") (pintype "passive"))
      (node (ref "IC1") (pin "47") (pinfunction "VSS_3_47") (pintype "passive"))
      (node (ref "IC1") (pin "63") (pinfunction "VSS_4_63") (pintype "passive"))
      (node (ref "J1") (pin "2") (pinfunction "2_2") (pintype "passive"))
      (node (ref "J1") (pin "3") (pinfunction "3_3") (pintype "passive"))
      (node (ref "J2") (pin "A1B12") (pinfunction "GND_A1B12") (pintype "power_in"))
      (node (ref "J2") (pin "B1A12") (pinfunction "GND_B1A12") (pintype "power_in"))
      (node (ref "J3") (pin "5") (pinfunction "GND_5") (pintype "passive"))
      (node (ref "Q3") (pin "S") (pinfunction "S_S") (pintype "passive"))
      (node (ref "R16") (pin "1") (pinfunction "1_1") (pintype "passive"))
      (node (ref "R17") (pin "1") (pinfunction "1_1") (pintype "passive"))
      (node (ref "R19") (pin "1") (pinfunction "1_1") (pintype "passive"))
      (node (ref "R21") (pin "2") (pinfunction "2_2") (pintype "passive"))
      (node (ref "R22") (pin "1") (pinfunction "1_1") (pintype "passive"))
      (node (ref "R24") (pin "1") (pinfunction "1_1") (pintype "passive"))
      (node (ref "R29") (pin "2") (pinfunction "2_2") (pintype "passive"))
      (node (ref "R30") (pin "2") (pinfunction "2_2") (pintype "passive"))
      (node (ref "R5") (pin "2") (pinfunction "2_2") (pintype "passive"))
      (node (ref "U1") (pin "2") (pinfunction "GND_2") (pintype "passive"))
      (node (ref "U2") (pin "19") (pinfunction "GND_19") (pintype "power_in"))
      (node (ref "U2") (pin "22") (pinfunction "GND_22") (pintype "power_in"))
      (node (ref "U2") (pin "25") (pinfunction "EP_25") (pintype "power_in"))
      (node (ref "U3") (pin "3") (pinfunction "GND_3") (pintype "power_in"))
      (node (ref "U3") (pin "4") (pinfunction "GND_4") (pintype "power_in"))
      (node (ref "X1") (pin "2") (pinfunction "2_2") (pintype "passive"))
      (node (ref "X1") (pin "4") (pinfunction "4_4") (pintype "passive"))
    )
    (net (code "42") (name "Net-(D1-PadK)") (class "Default")
      (node (ref "D1") (pin "K") (pinfunction "K_K") (pintype "passive"))
      (node (ref "R14") (pin "1") (pinfunction "1_1") (pintype "passive"))
    )
    (net (code "43") (name "Net-(J2-CC1)") (class "Default")
      (node (ref "J2") (pin "A5") (pinfunction "CC1_A5") (pintype "passive"))
      (node (ref "U2") (pin "15") (pinfunction "CC1_15") (pintype "bidirectional"))
    )
    (net (code "44") (name "Net-(J2-CC2)") (class "Default")
      (node (ref "J2") (pin "B5") (pinfunction "CC2_B5") (pintype "tri_state"))
      (node (ref "U2") (pin "14") (pinfunction "CC2_14") (pintype "bidirectional"))
    )
    (net (code "45") (name "Net-(Q1-S)") (class "Default")
      (node (ref "Q1") (pin "3") (pinfunction "S_3") (pintype "passive"))
      (node (ref "Q2") (pin "3") (pinfunction "S_3") (pintype "passive"))
    )
    (net (code "46") (name "Net-(Q3-PadD)") (class "Default")
      (node (ref "Q3") (pin "D") (pinfunction "D_D") (pintype "passive"))
      (node (ref "R14") (pin "2") (pinfunction "2_2") (pintype "passive"))
    )
    (net (code "47") (name "Net-(U1-OUT)") (class "Default")
      (node (ref "R8") (pin "2") (pinfunction "2_2") (pintype "passive"))
      (node (ref "U1") (pin "1") (pinfunction "OUT_1") (pintype "passive"))
    )
    (net (code "48") (name "unconnected-(IC1-BOOT0-Pad60)") (class "Default")
      (node (ref "IC1") (pin "60") (pinfunction "BOOT0_60") (pintype "passive"))
    )
    (net (code "49") (name "unconnected-(IC1-PA0-Pad14)") (class "Default")
      (node (ref "IC1") (pin "14") (pinfunction "PA0_14") (pintype "passive"))
    )
    (net (code "50") (name "unconnected-(IC1-PA3-Pad17)") (class "Default")
      (node (ref "IC1") (pin "17") (pinfunction "PA3_17") (pintype "passive"))
    )
    (net (code "51") (name "unconnected-(IC1-PA4-Pad20)") (class "Default")
      (node (ref "IC1") (pin "20") (pinfunction "PA4_20") (pintype "passive"))
    )
    (net (code "52") (name "unconnected-(IC1-PA5-Pad21)") (class "Default")
      (node (ref "IC1") (pin "21") (pinfunction "PA5_21") (pintype "passive"))
    )
    (net (code "53") (name "unconnected-(IC1-PA6-Pad22)") (class "Default")
      (node (ref "IC1") (pin "22") (pinfunction "PA6_22") (pintype "passive"))
    )
    (net (code "54") (name "unconnected-(IC1-PA7-Pad23)") (class "Default")
      (node (ref "IC1") (pin "23") (pinfunction "PA7_23") (pintype "passive"))
    )
    (net (code "55") (name "unconnected-(IC1-PB1-Pad27)") (class "Default")
      (node (ref "IC1") (pin "27") (pinfunction "PB1_27") (pintype "passive"))
    )
    (net (code "56") (name "unconnected-(IC1-PB2-Pad28)") (class "Default")
      (node (ref "IC1") (pin "28") (pinfunction "PB2_28") (pintype "passive"))
    )
    (net (code "57") (name "unconnected-(IC1-PB4-Pad56)") (class "Default")
      (node (ref "IC1") (pin "56") (pinfunction "PB4_56") (pintype "passive"))
    )
    (net (code "58") (name "unconnected-(IC1-PB5-Pad57)") (class "Default")
      (node (ref "IC1") (pin "57") (pinfunction "PB5_57") (pintype "passive"))
    )
    (net (code "59") (name "unconnected-(IC1-PB6-Pad58)") (class "Default")
      (node (ref "IC1") (pin "58") (pinfunction "PB6_58") (pintype "passive"))
    )
    (net (code "60") (name "unconnected-(IC1-PB7-Pad59)") (class "Default")
      (node (ref "IC1") (pin "59") (pinfunction "PB7_59") (pintype "passive"))
    )
    (net (code "61") (name "unconnected-(IC1-PB8-Pad61)") (class "Default")
      (node (ref "IC1") (pin "61") (pinfunction "PB8_61") (pintype "passive"))
    )
    (net (code "62") (name "unconnected-(IC1-PB9-Pad62)") (class "Default")
      (node (ref "IC1") (pin "62") (pinfunction "PB9_62") (pintype "passive"))
    )
    (net (code "63") (name "unconnected-(IC1-PB10-Pad29)") (class "Default")
      (node (ref "IC1") (pin "29") (pinfunction "PB10_29") (pintype "passive"))
    )
    (net (code "64") (name "unconnected-(IC1-PB12-Pad33)") (class "Default")
      (node (ref "IC1") (pin "33") (pinfunction "PB12_33") (pintype "passive"))
    )
    (net (code "65") (name "unconnected-(IC1-PB13-Pad34)") (class "Default")
      (node (ref "IC1") (pin "34") (pinfunction "PB13_34") (pintype "passive"))
    )
    (net (code "66") (name "unconnected-(IC1-PB14-Pad35)") (class "Default")
      (node (ref "IC1") (pin "35") (pinfunction "PB14_35") (pintype "passive"))
    )
    (net (code "67") (name "unconnected-(IC1-PB15-Pad36)") (class "Default")
      (node (ref "IC1") (pin "36") (pinfunction "PB15_36") (pintype "passive"))
    )
    (net (code "68") (name "unconnected-(IC1-PC0-Pad8)") (class "Default")
      (node (ref "IC1") (pin "8") (pinfunction "PC0_8") (pintype "passive"))
    )
    (net (code "69") (name "unconnected-(IC1-PC1-Pad9)") (class "Default")
      (node (ref "IC1") (pin "9") (pinfunction "PC1_9") (pintype "passive"))
    )
    (net (code "70") (name "unconnected-(IC1-PC2-Pad10)") (class "Default")
      (node (ref "IC1") (pin "10") (pinfunction "PC2_10") (pintype "passive"))
    )
    (net (code "71") (name "unconnected-(IC1-PC3-Pad11)") (class "Default")
      (node (ref "IC1") (pin "11") (pinfunction "PC3_11") (pintype "passive"))
    )
    (net (code "72") (name "unconnected-(IC1-PC4-Pad24)") (class "Default")
      (node (ref "IC1") (pin "24") (pinfunction "PC4_24") (pintype "passive"))
    )
    (net (code "73") (name "unconnected-(IC1-PC5-Pad25)") (class "Default")
      (node (ref "IC1") (pin "25") (pinfunction "PC5_25") (pintype "passive"))
    )
    (net (code "74") (name "unconnected-(IC1-PC6-Pad37)") (class "Default")
      (node (ref "IC1") (pin "37") (pinfunction "PC6_37") (pintype "passive"))
    )
    (net (code "75") (name "unconnected-(IC1-PC7-Pad38)") (class "Default")
      (node (ref "IC1") (pin "38") (pinfunction "PC7_38") (pintype "passive"))
    )
    (net (code "76") (name "unconnected-(IC1-PC8-Pad39)") (class "Default")
      (node (ref "IC1") (pin "39") (pinfunction "PC8_39") (pintype "passive"))
    )
    (net (code "77") (name "unconnected-(IC1-PC10-Pad51)") (class "Default")
      (node (ref "IC1") (pin "51") (pinfunction "PC10_51") (pintype "passive"))
    )
    (net (code "78") (name "unconnected-(IC1-PC13-Pad2)") (class "Default")
      (node (ref "IC1") (pin "2") (pinfunction "PC13_2") (pintype "passive"))
    )
    (net (code "79") (name "unconnected-(IC1-PC14-_OSC32_IN-Pad3)") (class "Default")
      (node (ref "IC1") (pin "3") (pinfunction "PC14-_OSC32_IN_3") (pintype "passive"))
    )
    (net (code "80") (name "unconnected-(IC1-PC15-_OSC32_OUT-Pad4)") (class "Default")
      (node (ref "IC1") (pin "4") (pinfunction "PC15-_OSC32_OUT_4") (pintype "passive"))
    )
    (net (code "81") (name "unconnected-(IC1-PD2-Pad54)") (class "Default")
      (node (ref "IC1") (pin "54") (pinfunction "PD2_54") (pintype "passive"))
    )
    (net (code "82") (name "unconnected-(J2-PadSH)") (class "Default")
      (node (ref "J2") (pin "SH") (pinfunction "SH_SH") (pintype "power_in"))
    )
    (net (code "83") (name "unconnected-(J2-SBU1-PadA8)") (class "Default")
      (node (ref "J2") (pin "A8") (pinfunction "SBU1_A8") (pintype "bidirectional+no_connect"))
    )
    (net (code "84") (name "unconnected-(J2-SBU2-PadB8)") (class "Default")
      (node (ref "J2") (pin "B8") (pinfunction "SBU2_B8") (pintype "bidirectional+no_connect"))
    )
    (net (code "85") (name "unconnected-(U2-D+-Pad17)") (class "Default")
      (node (ref "U2") (pin "17") (pinfunction "D+_17") (pintype "passive"))
    )
    (net (code "86") (name "unconnected-(U2-D--Pad16)") (class "Default")
      (node (ref "U2") (pin "16") (pinfunction "D-_16") (pintype "passive"))
    )
    (net (code "87") (name "unconnected-(U2-DNU1-Pad20)") (class "Default")
      (node (ref "U2") (pin "20") (pinfunction "DNU1_20") (pintype "passive+no_connect"))
    )
    (net (code "88") (name "unconnected-(U2-DNU2-Pad21)") (class "Default")
      (node (ref "U2") (pin "21") (pinfunction "DNU2_21") (pintype "passive+no_connect"))
    )
  )
)
